# Server_Main_Power.net
KiCad netlist of a schematic drawn in Altium Designer
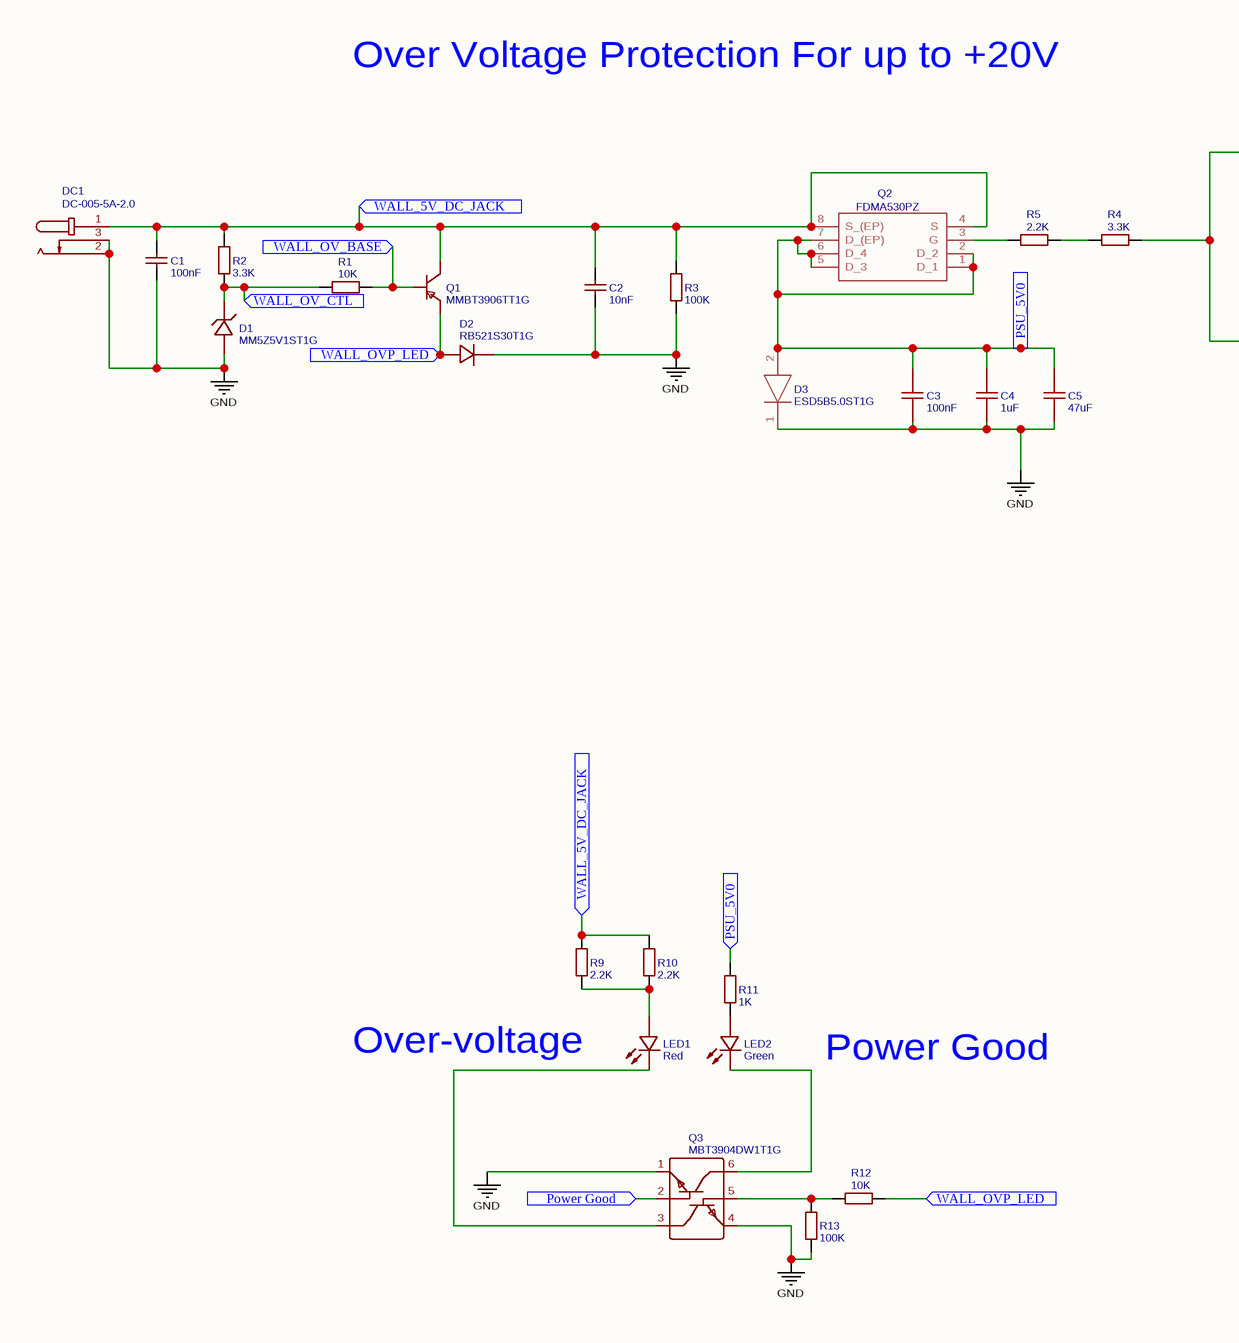
[diagram p0: Server Main Power.schdoc, left]
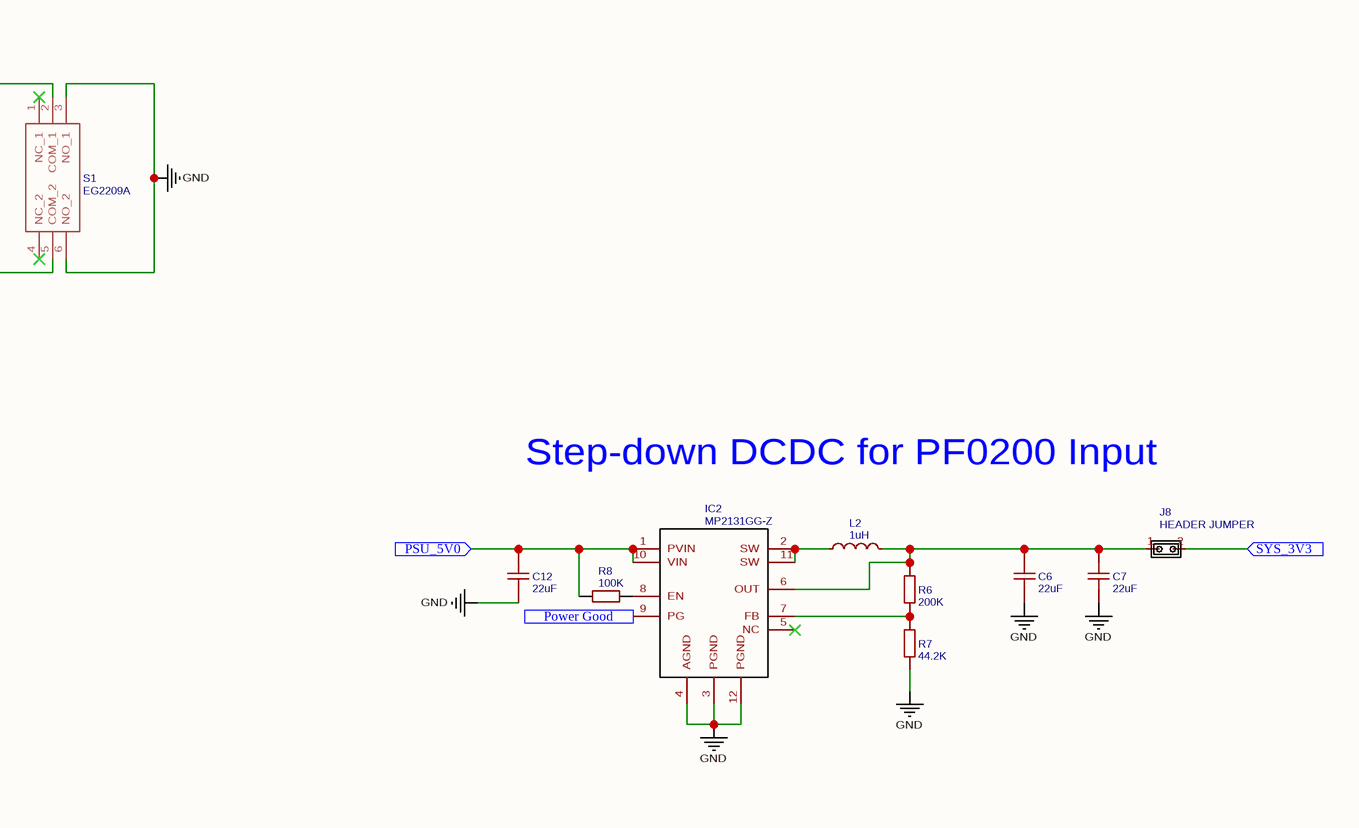
[diagram p1: Server Main Power.schdoc, right]

(export (version "E")
  (design (tool "Eeschema 10.0.6"))
  (components
    (comp (ref "C1")
      (value "100nF")
      (fields
        (field (name "BOM_MANUFACTURER PART") "CL31B104KBCNNNC")
        (field (name "BOM_SUPPLIER PART") "C24497")
      )
      (libsource (lib "") (part "root_1_100nF__1"))
    )
    (comp (ref "C2")
      (value "10nF")
      (fields
        (field (name "BOM_MANUFACTURER PART") "CL05B103KB5NNNC")
        (field (name "BOM_SUPPLIER PART") "C15195")
      )
      (libsource (lib "altium-import") (part "root_1_10nF_"))
    )
    (comp (ref "C3")
      (value "100nF")
      (fields
        (field (name "BOM_MANUFACTURER PART") "CC0603KRX7R9BB104")
        (field (name "BOM_SUPPLIER PART") "C14663")
      )
      (libsource (lib "altium-import") (part "root_1_100nF_"))
    )
    (comp (ref "C4")
      (value "1uF")
      (fields
        (field (name "BOM_MANUFACTURER PART") "CL05A105KA5NQNC")
        (field (name "BOM_SUPPLIER PART") "C52923")
      )
      (libsource (lib "altium-import") (part "root_1_1uF_"))
    )
    (comp (ref "C5")
      (value "47uF")
      (fields
        (field (name "BOM_MANUFACTURER PART") "CL31A476MPHNNNE")
        (field (name "BOM_SUPPLIER PART") "C96123")
      )
      (libsource (lib "altium-import") (part "root_1_47uF_"))
    )
    (comp (ref "C6")
      (value "22uF")
      (fields (field (name "BOM_SUPPLIER PART") "C19704") (field (name "CONTRIBUTOR") "LCSC"))
      (libsource (lib "altium-import") (part "root_2_22uF_"))
    )
    (comp (ref "C7")
      (value "22uF")
      (fields (field (name "BOM_SUPPLIER PART") "C19704") (field (name "CONTRIBUTOR") "LCSC"))
      (libsource (lib "altium-import") (part "root_0_22uF_"))
    )
    (comp (ref "C12")
      (value "22uF")
      (fields (field (name "BOM_SUPPLIER PART") "C19704") (field (name "CONTRIBUTOR") "LCSC"))
      (libsource (lib "altium-import") (part "root_0_22uF_"))
    )
    (comp (ref "D1")
      (value "MM5Z5V1ST1G")
      (fields (field (name "BOM_SUPPLIER PART") "C94383"))
      (libsource (lib "altium-import") (part "root_3_MM5Z5V1ST1G_"))
    )
    (comp (ref "D2")
      (value "RB521S30T1G")
      (fields (field (name "BOM_SUPPLIER PART") "C145179") (field (name "CONTRIBUTOR") "LCSC"))
      (libsource (lib "altium-import") (part "root_2_RB521S30T1G_"))
    )
    (comp (ref "D3")
      (value "ESD5B5.0ST1G")
      (fields (field (name "CONTRIBUTOR") "Ke'Ondrae_Mell"))
      (libsource (lib "altium-import") (part "root_1_ESD5B5.0ST1G_"))
    )
    (comp (ref "DC1")
      (value "DC-005-5A-2.0")
      (fields (field (name "BOM_SUPPLIER PART") "C381116") (field (name "CONTRIBUTOR") "LCSC"))
      (libsource (lib "altium-import") (part "root_0_DC-005-5A-2.0_"))
    )
    (comp (ref "IC2")
      (value "MP2131GG-Z")
      (fields (field (name "CONTRIBUTOR") "Ke'Ondrae_Mell"))
      (libsource (lib "altium-import") (part "root_0_MP2131GG-Z_"))
    )
    (comp (ref "J8")
      (value "HEADER JUMPER")
      (fields (field (name "CONTRIBUTOR") "iinnovations"))
      (libsource (lib "altium-import") (part "root_0_HEADER JUMPER_"))
    )
    (comp (ref "L2")
      (value "1uH")
      (fields
        (field (name "BOM_SUPPLIER PART") "C151871")
        (field (name "BOM_MANUFACTURER PART") "MWSA1004-1R0MT")
        (field (name "CONTRIBUTOR") "LCSC")
      )
      (libsource (lib "altium-import") (part "root_0_1uH_"))
    )
    (comp (ref "LED1")
      (value "Red")
      (fields
        (field (name "BOM_MANUFACTURER PART") "FC-2012HRK-620D")
        (field (name "BOM_SUPPLIER PART") "C84256")
      )
      (libsource (lib "altium-import") (part "root_1_Red_"))
    )
    (comp (ref "LED2")
      (value "Green")
      (fields
        (field (name "BOM_MANUFACTURER PART") "FC-2012HRK-620D")
        (field (name "BOM_SUPPLIER PART") "C84256")
      )
      (libsource (lib "altium-import") (part "root_1_Green_"))
    )
    (comp (ref "Q1")
      (value "MMBT3906TT1G")
      (fields (field (name "BOM_SUPPLIER PART") "C82042"))
      (libsource (lib "altium-import") (part "root_0_MMBT3906TT1G_"))
    )
    (comp (ref "Q2")
      (value "FDMA530PZ")
      (fields (field (name "CONTRIBUTOR") "Ke'Ondrae_Mell"))
      (libsource (lib "altium-import") (part "root_2_FDMA530PZ_"))
    )
    (comp (ref "Q3")
      (value "MBT3904DW1T1G")
      (fields (field (name "BOM_SUPPLIER PART") "C110150"))
      (libsource (lib "altium-import") (part "root_1_MBT3904DW1T1G_"))
    )
    (comp (ref "R1")
      (value "10K")
      (fields
        (field (name "BOM_MANUFACTURER PART") "0603WAF1002T5E")
        (field (name "BOM_SUPPLIER PART") "C25804")
      )
      (libsource (lib "altium-import") (part "root_0_10K_"))
    )
    (comp (ref "R2")
      (value "3.3K")
      (fields
        (field (name "BOM_MANUFACTURER PART") "0402WGF3301TCE")
        (field (name "BOM_SUPPLIER PART") "C25890")
      )
      (libsource (lib "altium-import") (part "root_1_3.3K_"))
    )
    (comp (ref "R3")
      (value "100K")
      (fields
        (field (name "BOM_MANUFACTURER PART") "0603WAF1003T5E")
        (field (name "BOM_SUPPLIER PART") "C25803")
      )
      (libsource (lib "altium-import") (part "root_1_100K_"))
    )
    (comp (ref "R4")
      (value "3.3K")
      (fields
        (field (name "BOM_MANUFACTURER PART") "0402WGF3301TCE")
        (field (name "BOM_SUPPLIER PART") "C25890")
      )
      (libsource (lib "altium-import") (part "root_2_3.3K_"))
    )
    (comp (ref "R5")
      (value "2.2K")
      (fields
        (field (name "BOM_MANUFACTURER PART") "0402WGF2201TCE")
        (field (name "BOM_SUPPLIER PART") "C25879")
      )
      (libsource (lib "altium-import") (part "root_2_2.2K_"))
    )
    (comp (ref "R6")
      (value "200K")
      (fields
        (field (name "BOM_MANUFACTURER PART") "TC0325F2003T5E")
        (field (name "BOM_SUPPLIER PART") "C133268")
        (field (name "CONTRIBUTOR") "LCSC")
      )
      (libsource (lib "altium-import") (part "root_1_200K_"))
    )
    (comp (ref "R7")
      (value "44.2K")
      (fields
        (field (name "BOM_SUPPLIER PART") "C247257")
        (field (name "BOM_MANUFACTURER PART") "1206W4F4422T5E")
        (field (name "CONTRIBUTOR") "LCSC")
      )
      (libsource (lib "altium-import") (part "root_1_44.2K_"))
    )
    (comp (ref "R8")
      (value "100K")
      (fields
        (field (name "BOM_MANUFACTURER PART") "0603WAF1003T5E")
        (field (name "BOM_SUPPLIER PART") "C25803")
      )
      (libsource (lib "altium-import") (part "root_0_100K_"))
    )
    (comp (ref "R9")
      (value "2.2K")
      (fields
        (field (name "BOM_MANUFACTURER PART") "RS-02K222JT")
        (field (name "BOM_SUPPLIER PART") "C140191")
      )
      (libsource (lib "altium-import") (part "root_1_2.2K_"))
    )
    (comp (ref "R10")
      (value "2.2K")
      (fields
        (field (name "BOM_MANUFACTURER PART") "RS-02K222JT")
        (field (name "BOM_SUPPLIER PART") "C140191")
      )
      (libsource (lib "altium-import") (part "root_1_2.2K_"))
    )
    (comp (ref "R11")
      (value "1K")
      (fields
        (field (name "BOM_MANUFACTURER PART") "0402WGF1001TCE")
        (field (name "BOM_SUPPLIER PART") "C11702")
      )
      (libsource (lib "altium-import") (part "root_1_1K_"))
    )
    (comp (ref "R12")
      (value "10K")
      (fields
        (field (name "BOM_MANUFACTURER PART") "0402WGF1002TCE")
        (field (name "BOM_SUPPLIER PART") "C25744")
      )
      (libsource (lib "altium-import") (part "root_0_10K_"))
    )
    (comp (ref "R13")
      (value "100K")
      (fields
        (field (name "BOM_MANUFACTURER PART") "0603WAF1003T5E")
        (field (name "BOM_SUPPLIER PART") "C25803")
      )
      (libsource (lib "altium-import") (part "root_1_100K_"))
    )
    (comp (ref "S1") (value "EG2209A") (libsource (lib "altium-import") (part "root_1_EG2209A_")))
  )
  (nets
    (net (code "1") (name "/PSU_5V0") (class "Default")
      (node (ref "C12") (pin "2") (pinfunction "2_2") (pintype "passive"))
      (node (ref "C3") (pin "2") (pinfunction "2_2") (pintype "passive"))
      (node (ref "C4") (pin "2") (pinfunction "2_2") (pintype "passive"))
      (node (ref "C5") (pin "2") (pinfunction "2_2") (pintype "passive"))
      (node (ref "D3") (pin "2") (pinfunction "A_2") (pintype "passive"))
      (node (ref "IC2") (pin "1") (pinfunction "PVIN_1") (pintype "passive"))
      (node (ref "IC2") (pin "10") (pinfunction "VIN_10") (pintype "passive"))
      (node (ref "Q2") (pin "1") (pinfunction "D_1_1") (pintype "passive"))
      (node (ref "Q2") (pin "2") (pinfunction "D_2_2") (pintype "passive"))
      (node (ref "Q2") (pin "5") (pinfunction "D_3_5") (pintype "passive"))
      (node (ref "Q2") (pin "6") (pinfunction "D_4_6") (pintype "passive"))
      (node (ref "Q2") (pin "7") (pinfunction "D_(EP)_7") (pintype "passive"))
      (node (ref "R11") (pin "2") (pinfunction "2_2") (pintype "passive"))
      (node (ref "R8") (pin "1") (pinfunction "1_1") (pintype "passive"))
    )
    (net (code "2") (name "/Power Good") (class "Default")
      (node (ref "IC2") (pin "9") (pinfunction "PG_9") (pintype "passive"))
      (node (ref "Q3") (pin "2") (pinfunction "2_2") (pintype "passive"))
    )
    (net (code "3") (name "/SYS_3V3") (class "Default")
      (node (ref "J8") (pin "2") (pinfunction "2_2") (pintype "passive"))
    )
    (net (code "4") (name "/WALL_5V_DC_JACK") (class "Default")
      (node (ref "C1") (pin "2") (pinfunction "2_2") (pintype "passive"))
      (node (ref "C2") (pin "2") (pinfunction "2_2") (pintype "passive"))
      (node (ref "DC1") (pin "1") (pinfunction "1_1") (pintype "passive"))
      (node (ref "Q1") (pin "3") (pinfunction "C_3") (pintype "passive"))
      (node (ref "Q2") (pin "4") (pinfunction "S_4") (pintype "passive"))
      (node (ref "Q2") (pin "8") (pinfunction "S_(EP)_8") (pintype "passive"))
      (node (ref "R10") (pin "2") (pinfunction "2_2") (pintype "passive"))
      (node (ref "R2") (pin "2") (pinfunction "2_2") (pintype "passive"))
      (node (ref "R3") (pin "2") (pinfunction "2_2") (pintype "passive"))
      (node (ref "R9") (pin "2") (pinfunction "2_2") (pintype "passive"))
    )
    (net (code "5") (name "/WALL_OVP_LED") (class "Default")
      (node (ref "D2") (pin "2") (pinfunction "A_2") (pintype "passive"))
      (node (ref "Q1") (pin "2") (pinfunction "E_2") (pintype "passive"))
      (node (ref "R12") (pin "2") (pinfunction "2_2") (pintype "passive"))
    )
    (net (code "6") (name "/WALL_OV_BASE") (class "Default")
      (node (ref "Q1") (pin "1") (pinfunction "B_1") (pintype "passive"))
      (node (ref "R1") (pin "2") (pinfunction "2_2") (pintype "passive"))
    )
    (net (code "7") (name "/WALL_OV_CTL") (class "Default")
      (node (ref "D1") (pin "1") (pinfunction "K_1") (pintype "passive"))
      (node (ref "R1") (pin "1") (pinfunction "1_1") (pintype "passive"))
      (node (ref "R2") (pin "1") (pinfunction "1_1") (pintype "passive"))
    )
    (net (code "8") (name "GND") (class "Default")
      (node (ref "C1") (pin "1") (pinfunction "1_1") (pintype "passive"))
      (node (ref "C12") (pin "1") (pinfunction "1_1") (pintype "passive"))
      (node (ref "C2") (pin "1") (pinfunction "1_1") (pintype "passive"))
      (node (ref "C3") (pin "1") (pinfunction "1_1") (pintype "passive"))
      (node (ref "C4") (pin "1") (pinfunction "1_1") (pintype "passive"))
      (node (ref "C5") (pin "1") (pinfunction "1_1") (pintype "passive"))
      (node (ref "C6") (pin "2") (pinfunction "2_2") (pintype "passive"))
      (node (ref "C7") (pin "1") (pinfunction "1_1") (pintype "passive"))
      (node (ref "D1") (pin "2") (pinfunction "A_2") (pintype "passive"))
      (node (ref "D2") (pin "1") (pinfunction "C_1") (pintype "passive"))
      (node (ref "D3") (pin "1") (pinfunction "K_1") (pintype "passive"))
      (node (ref "DC1") (pin "2") (pinfunction "2_2") (pintype "passive"))
      (node (ref "DC1") (pin "3") (pinfunction "3_3") (pintype "passive"))
      (node (ref "IC2") (pin "12") (pinfunction "PGND_12") (pintype "passive"))
      (node (ref "IC2") (pin "3") (pinfunction "PGND_3") (pintype "passive"))
      (node (ref "IC2") (pin "4") (pinfunction "AGND_4") (pintype "passive"))
      (node (ref "Q3") (pin "1") (pinfunction "1_1") (pintype "passive"))
      (node (ref "Q3") (pin "4") (pinfunction "4_4") (pintype "passive"))
      (node (ref "R13") (pin "1") (pinfunction "1_1") (pintype "passive"))
      (node (ref "R3") (pin "1") (pinfunction "1_1") (pintype "passive"))
      (node (ref "R7") (pin "1") (pinfunction "1_1") (pintype "passive"))
      (node (ref "S1") (pin "3") (pinfunction "NO_1_3") (pintype "passive"))
      (node (ref "S1") (pin "6") (pinfunction "NO_2_6") (pintype "passive"))
    )
    (net (code "9") (name "Net-(IC2-EN)") (class "Default")
      (node (ref "IC2") (pin "8") (pinfunction "EN_8") (pintype "passive"))
      (node (ref "R8") (pin "2") (pinfunction "2_2") (pintype "passive"))
    )
    (net (code "10") (name "Net-(IC2-FB)") (class "Default")
      (node (ref "IC2") (pin "7") (pinfunction "FB_7") (pintype "passive"))
      (node (ref "R6") (pin "1") (pinfunction "1_1") (pintype "passive"))
      (node (ref "R7") (pin "2") (pinfunction "2_2") (pintype "passive"))
    )
    (net (code "11") (name "Net-(IC2-OUT)") (class "Default")
      (node (ref "C6") (pin "1") (pinfunction "1_1") (pintype "passive"))
      (node (ref "C7") (pin "2") (pinfunction "2_2") (pintype "passive"))
      (node (ref "IC2") (pin "6") (pinfunction "OUT_6") (pintype "passive"))
      (node (ref "J8") (pin "1") (pinfunction "1_1") (pintype "passive"))
      (node (ref "L2") (pin "2") (pinfunction "2_2") (pintype "passive"))
      (node (ref "R6") (pin "2") (pinfunction "2_2") (pintype "passive"))
    )
    (net (code "12") (name "Net-(IC2-SW-Pad11)") (class "Default")
      (node (ref "IC2") (pin "11") (pinfunction "SW_11") (pintype "passive"))
      (node (ref "IC2") (pin "2") (pinfunction "SW_2") (pintype "passive"))
      (node (ref "L2") (pin "1") (pinfunction "1_1") (pintype "passive"))
    )
    (net (code "13") (name "Net-(LED1-+)") (class "Default")
      (node (ref "LED1") (pin "2") (pinfunction "+_2") (pintype "passive"))
      (node (ref "R10") (pin "1") (pinfunction "1_1") (pintype "passive"))
      (node (ref "R9") (pin "1") (pinfunction "1_1") (pintype "passive"))
    )
    (net (code "14") (name "Net-(LED1--)") (class "Default")
      (node (ref "LED1") (pin "1") (pinfunction "-_1") (pintype "passive"))
      (node (ref "Q3") (pin "3") (pinfunction "3_3") (pintype "passive"))
    )
    (net (code "15") (name "Net-(LED2-+)") (class "Default")
      (node (ref "LED2") (pin "2") (pinfunction "+_2") (pintype "passive"))
      (node (ref "R11") (pin "1") (pinfunction "1_1") (pintype "passive"))
    )
    (net (code "16") (name "Net-(LED2--)") (class "Default")
      (node (ref "LED2") (pin "1") (pinfunction "-_1") (pintype "passive"))
      (node (ref "Q3") (pin "6") (pinfunction "6_6") (pintype "passive"))
    )
    (net (code "17") (name "Net-(Q2-G)") (class "Default")
      (node (ref "Q2") (pin "3") (pinfunction "G_3") (pintype "passive"))
      (node (ref "R5") (pin "2") (pinfunction "2_2") (pintype "passive"))
    )
    (net (code "18") (name "Net-(Q3-Pad5)") (class "Default")
      (node (ref "Q3") (pin "5") (pinfunction "5_5") (pintype "passive"))
      (node (ref "R12") (pin "1") (pinfunction "1_1") (pintype "passive"))
      (node (ref "R13") (pin "2") (pinfunction "2_2") (pintype "passive"))
    )
    (net (code "19") (name "Net-(R4-Pad2)") (class "Default")
      (node (ref "R4") (pin "2") (pinfunction "2_2") (pintype "passive"))
      (node (ref "R5") (pin "1") (pinfunction "1_1") (pintype "passive"))
    )
    (net (code "20") (name "Net-(S1-COM_1)") (class "Default")
      (node (ref "R4") (pin "1") (pinfunction "1_1") (pintype "passive"))
      (node (ref "S1") (pin "2") (pinfunction "COM_1_2") (pintype "passive"))
      (node (ref "S1") (pin "5") (pinfunction "COM_2_5") (pintype "passive"))
    )
    (net (code "21") (name "unconnected-(IC2-NC-Pad5)") (class "Default")
      (node (ref "IC2") (pin "5") (pinfunction "NC_5") (pintype "passive+no_connect"))
    )
    (net (code "22") (name "unconnected-(S1-NC_1-Pad1)") (class "Default")
      (node (ref "S1") (pin "1") (pinfunction "NC_1_1") (pintype "passive+no_connect"))
    )
    (net (code "23") (name "unconnected-(S1-NC_2-Pad4)") (class "Default")
      (node (ref "S1") (pin "4") (pinfunction "NC_2_4") (pintype "passive+no_connect"))
    )
  )
)
